# Sheet1.net
KiCad netlist of a schematic drawn in Altium Designer
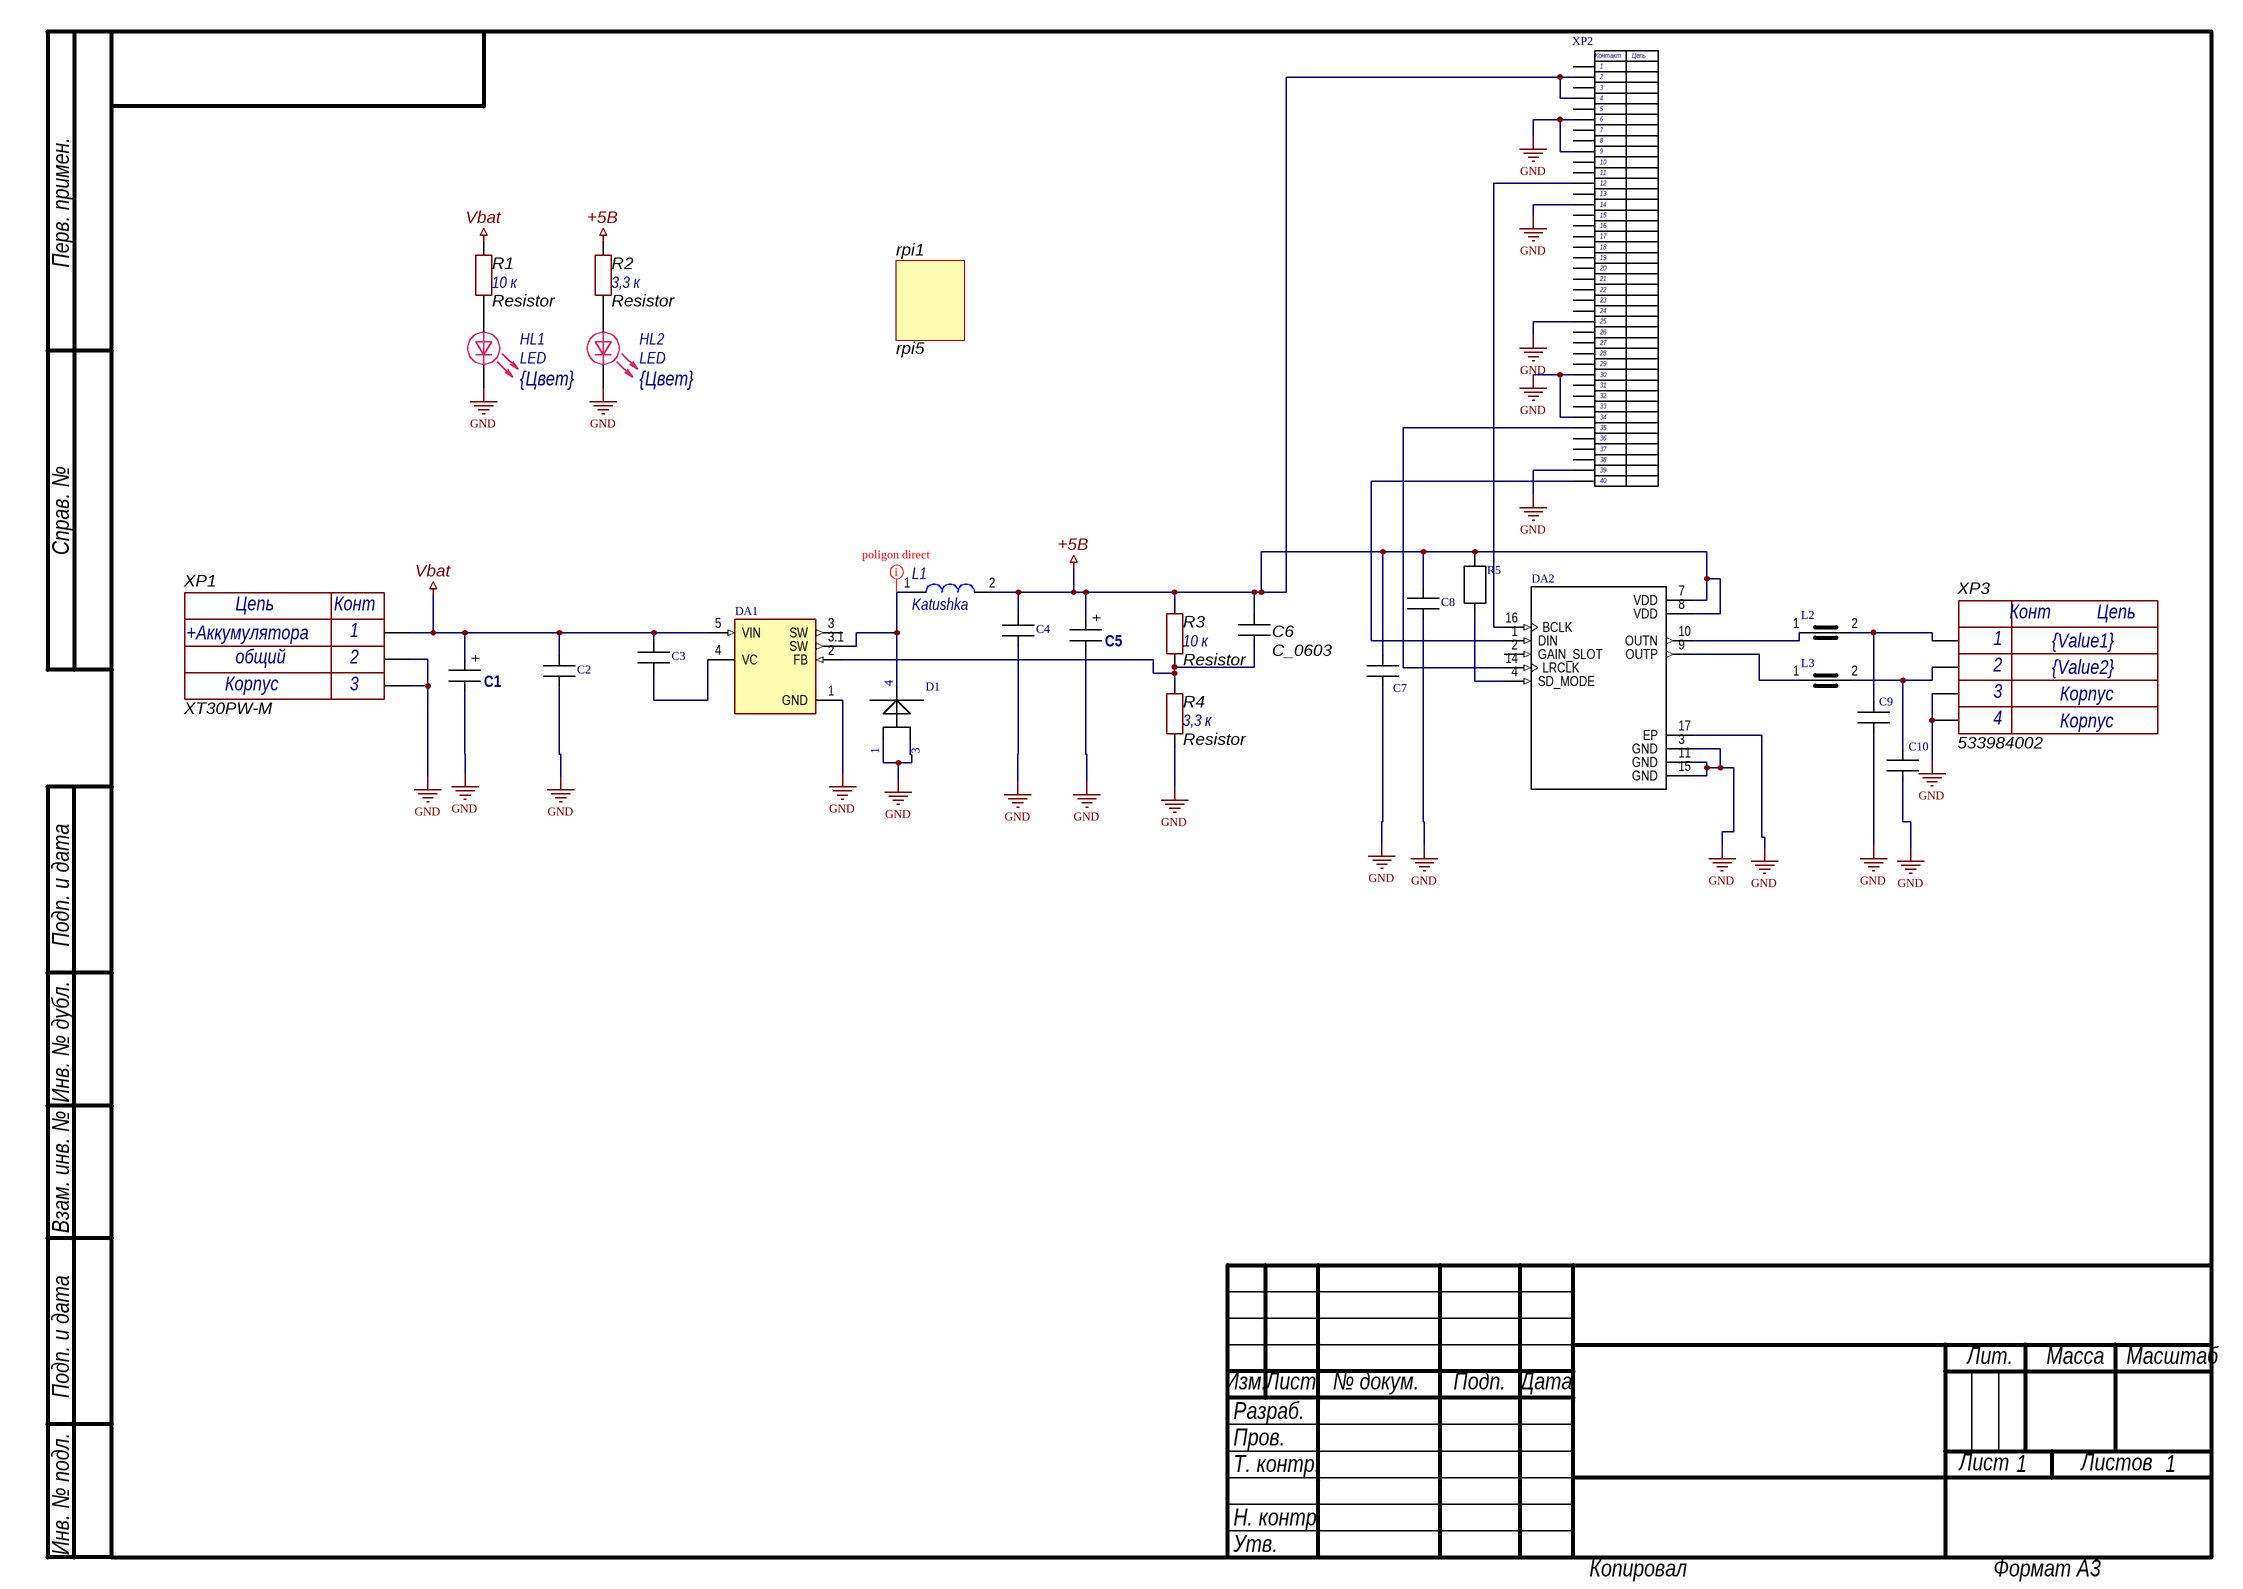
[diagram p0: Sheet1.SchDoc]

(export (version "E")
  (design (tool "Eeschema 10.0.6"))
  (components
    (comp (ref "C1")
      (value "C Al SMD 220mcF")
      (footprint "ECAP 10-10")
      (description "Конденсатор ECAP")
      (libsource (lib "Schlib1") (part "C Al SMD"))
    )
    (comp (ref "C2")
      (value "С_0.1uF")
      (footprint "CAP 0603 3D")
      (description "0.1мкФ")
      (libsource (lib "Schlib1") (part "С_0603"))
    )
    (comp (ref "C3")
      (value "С_0.1uF")
      (footprint "CAP 0603 3D")
      (description "0.1мкФ")
      (libsource (lib "Schlib1") (part "С_0603"))
    )
    (comp (ref "C4")
      (value "С_0.1uF")
      (footprint "CAP 0603 3D")
      (description "0.1мкФ")
      (libsource (lib "Schlib1") (part "С_0603"))
    )
    (comp (ref "C5")
      (value "C Al SMD 220mkf")
      (footprint "ECAP 10-10")
      (description "Конденсатор ECAP")
      (libsource (lib "Schlib1") (part "C Al SMD"))
    )
    (comp (ref "C6")
      (value "С_0603")
      (footprint "CAP 0603 3D")
      (description "Конденсатор керамика 0.33нФ")
      (libsource (lib "Schlib1") (part "С_0603"))
    )
    (comp (ref "C7")
      (value "С_0.1uF")
      (footprint "CAP 0603 3D")
      (description "0.1мкФ")
      (libsource (lib "Schlib1") (part "С_0603"))
    )
    (comp (ref "C8")
      (value "С_0.1uF")
      (footprint "CAP 0603 3D")
      (description "0.1мкФ")
      (libsource (lib "Schlib1") (part "С_0603"))
    )
    (comp (ref "C9") (value "С_220pF") (footprint "CAP 0603 3D") (libsource (lib "Schlib1") (part "С_0603")))
    (comp (ref "C10") (value "С_220pF") (footprint "CAP 0603 3D") (libsource (lib "Schlib1") (part "С_0603")))
    (comp (ref "D1")
      (value "LF33CDT")
      (footprint "DPACK")
      (description "Linear Voltage Regulator IC Positive Fixed 1 Output 500mA DPAK")
      (fields (field (name "MF") "STMicroelectronics"))
      (libsource (lib "Schlib1") (part "LF33CDT"))
    )
    (comp (ref "DA1")
      (value "XL4015")
      (footprint "CONV_XL4015")
      (description "5A 180KHz 36V Buck DC to DC Converter")
      (fields (field (name "MF") "XLSEMI"))
      (libsource (lib "Schlib1") (part "XL4015"))
    )
    (comp (ref "DA2")
      (value "MAX98357AETE+T")
      (footprint "QFN50P300X300X80-17N")
      (description "Tiny, Low-Cost, PCM Class D Amplifier with Class AB Performance")
      (fields (field (name "MF") "Analog Devices"))
      (libsource (lib "Schlib1") (part "MAX98357AETE+T"))
    )
    (comp (ref "HL1")
      (value "LED")
      (footprint "0805D")
      (description "Светодиод")
      (fields (field (name "COLOR") "{Цвет}"))
      (libsource (lib "Hydrolib") (part "LED"))
    )
    (comp (ref "HL2")
      (value "LED")
      (footprint "0805D")
      (description "Светодиод")
      (fields (field (name "COLOR") "{Цвет}"))
      (libsource (lib "Hydrolib") (part "LED"))
    )
    (comp (ref "L1") (value "Katushka") (footprint "Katushka") (libsource (lib "Schlib1") (part "Katushka")))
    (comp (ref "L2")
      (value "Z")
      (footprint "Ferrit_1210")
      (description "Феррит")
      (libsource (lib "Schlib1") (part "Z"))
    )
    (comp (ref "L3")
      (value "Z")
      (footprint "Ferrit_1210")
      (description "Феррит")
      (libsource (lib "Schlib1") (part "Z"))
    )
    (comp (ref "R1")
      (value "Resistor")
      (footprint "0603R")
      (description "Резистор номиналом 10 кОм и точностью 1%")
      (fields
        (field (name "ALTIUM_VALUE") "10 к")
        (field (name "PART NUMBER") "Resistor_10k_1_0603")
        (field (name "TOLERANCE") "1%")
      )
      (libsource (lib "Hydrolib") (part "Resistor"))
    )
    (comp (ref "R2")
      (value "Resistor")
      (footprint "0603R")
      (description "Резистор номиналом 3,3 кОм и точностью 1%")
      (fields
        (field (name "ALTIUM_VALUE") "3,3 к")
        (field (name "PART NUMBER") "Resistor_3.3k_1_0603")
        (field (name "TOLERANCE") "1%")
      )
      (libsource (lib "Hydrolib") (part "Resistor"))
    )
    (comp (ref "R3")
      (value "Resistor")
      (footprint "0603R")
      (description "Резистор номиналом 10 кОм и точностью 1%")
      (fields
        (field (name "ALTIUM_VALUE") "10 к")
        (field (name "PART NUMBER") "Resistor_10k_1_0603")
        (field (name "TOLERANCE") "1%")
      )
      (libsource (lib "Hydrolib") (part "Resistor"))
    )
    (comp (ref "R4")
      (value "Resistor")
      (footprint "0603R")
      (description "Резистор номиналом 3,3 кОм и точностью 1%")
      (fields
        (field (name "ALTIUM_VALUE") "3,3 к")
        (field (name "PART NUMBER") "Resistor_3.3k_1_0603")
        (field (name "TOLERANCE") "1%")
      )
      (libsource (lib "Hydrolib") (part "Resistor"))
    )
    (comp (ref "R5") (value "R_0603") (footprint "Res_0603 3D") (libsource (lib "Schlib1") (part "R_0603")))
    (comp (ref "rpi1") (value "rpi5") (footprint "rpi5") (libsource (lib "Schlib1") (part "rpi5")))
    (comp (ref "XP1")
      (value "XT30PW-M")
      (footprint "XT30PW-M")
      (description "30 А (15 продолжительно), 2 контакта разъем угловой отец")
      (fields
        (field (name "VALUE3") "Корпус")
        (field (name "VALUE2") "общий")
        (field (name "VALUE1") "+Аккумулятора")
      )
      (libsource (lib "Hydrolib") (part "Polar_Conn_Shield"))
    )
    (comp (ref "XP2") (value "PBD_40") (footprint "PBD40_8.5") (libsource (lib "Schlib1") (part "PBD_40")))
    (comp (ref "XP3")
      (value "533984002")
      (footprint "Picoblade_533984002")
      (description "2pin, 1.25mm, вилка, PicoBlade, на плату, SMT")
      (fields
        (field (name "VALUE3") "Корпус")
        (field (name "VALUE2") "{Value2}")
        (field (name "VALUE4") "Корпус")
        (field (name "VALUE1") "{Value1}")
        (field (name "PART NUMBER") "Picoblade_533984002")
      )
      (libsource (lib "Hydrolib") (part "Conn_2pin_2shield"))
    )
  )
  (nets
    (net (code "1") (name "+5В") (class "Default")
      (node (ref "C4") (pin "1") (pinfunction "-_1") (pintype "passive"))
      (node (ref "C5") (pin "2") (pinfunction "+_2") (pintype "passive"))
      (node (ref "C6") (pin "1") (pinfunction "-_1") (pintype "passive"))
      (node (ref "C7") (pin "1") (pinfunction "-_1") (pintype "passive"))
      (node (ref "C8") (pin "1") (pinfunction "-_1") (pintype "passive"))
      (node (ref "DA2") (pin "7") (pinfunction "VDD_7") (pintype "power_in"))
      (node (ref "DA2") (pin "8") (pinfunction "VDD_8") (pintype "power_in"))
      (node (ref "L1") (pin "2") (pintype "passive"))
      (node (ref "R2") (pin "2") (pinfunction "2_2") (pintype "passive"))
      (node (ref "R3") (pin "2") (pinfunction "2_2") (pintype "passive"))
      (node (ref "R5") (pin "2") (pintype "passive"))
      (node (ref "XP2") (pin "2") (pinfunction "2_2") (pintype "passive"))
      (node (ref "XP2") (pin "4") (pinfunction "4_4") (pintype "passive"))
    )
    (net (code "2") (name "GND") (class "Default")
      (node (ref "C1") (pin "1") (pinfunction "-_1") (pintype "passive"))
      (node (ref "C10") (pin "2") (pinfunction "+_2") (pintype "passive"))
      (node (ref "C2") (pin "2") (pinfunction "+_2") (pintype "passive"))
      (node (ref "C4") (pin "2") (pinfunction "+_2") (pintype "passive"))
      (node (ref "C5") (pin "1") (pinfunction "-_1") (pintype "passive"))
      (node (ref "C7") (pin "2") (pinfunction "+_2") (pintype "passive"))
      (node (ref "C8") (pin "2") (pinfunction "+_2") (pintype "passive"))
      (node (ref "C9") (pin "2") (pinfunction "+_2") (pintype "passive"))
      (node (ref "D1") (pin "1") (pinfunction "1_1") (pintype "passive"))
      (node (ref "D1") (pin "3") (pinfunction "3_3") (pintype "passive"))
      (node (ref "DA1") (pin "1") (pinfunction "GND_1") (pintype "power_in"))
      (node (ref "DA2") (pin "11") (pinfunction "GND_11") (pintype "power_in"))
      (node (ref "DA2") (pin "15") (pinfunction "GND_15") (pintype "power_in"))
      (node (ref "DA2") (pin "17") (pinfunction "EP_17") (pintype "power_in"))
      (node (ref "DA2") (pin "3") (pinfunction "GND_3") (pintype "power_in"))
      (node (ref "HL1") (pin "2") (pinfunction "2_2") (pintype "passive"))
      (node (ref "HL2") (pin "2") (pinfunction "2_2") (pintype "passive"))
      (node (ref "R4") (pin "1") (pinfunction "1_1") (pintype "passive"))
      (node (ref "XP1") (pin "0") (pinfunction "0_0") (pintype "passive"))
      (node (ref "XP1") (pin "N") (pinfunction "N_N") (pintype "passive"))
      (node (ref "XP2") (pin "14") (pinfunction "14_14") (pintype "passive"))
      (node (ref "XP2") (pin "25") (pinfunction "25_25") (pintype "passive"))
      (node (ref "XP2") (pin "30") (pinfunction "30_30") (pintype "passive"))
      (node (ref "XP2") (pin "34") (pinfunction "34_34") (pintype "passive"))
      (node (ref "XP2") (pin "39") (pinfunction "39_39") (pintype "passive"))
      (node (ref "XP2") (pin "6") (pinfunction "6_6") (pintype "passive"))
      (node (ref "XP2") (pin "9") (pinfunction "9_9") (pintype "passive"))
      (node (ref "XP3") (pin "3") (pinfunction "3_3") (pintype "passive"))
      (node (ref "XP3") (pin "4") (pinfunction "4_4") (pintype "passive"))
    )
    (net (code "3") (name "Net-(C3-+)") (class "Default")
      (node (ref "C3") (pin "2") (pinfunction "+_2") (pintype "passive"))
      (node (ref "DA1") (pin "4") (pinfunction "VC_4") (pintype "passive"))
    )
    (net (code "4") (name "Net-(C6-+)") (class "Default")
      (node (ref "C6") (pin "2") (pinfunction "+_2") (pintype "passive"))
      (node (ref "DA1") (pin "2") (pinfunction "FB_2") (pintype "input"))
      (node (ref "R3") (pin "1") (pinfunction "1_1") (pintype "passive"))
      (node (ref "R4") (pin "2") (pinfunction "2_2") (pintype "passive"))
    )
    (net (code "5") (name "Net-(C9--)") (class "Default")
      (node (ref "C9") (pin "1") (pinfunction "-_1") (pintype "passive"))
      (node (ref "L2") (pin "2") (pinfunction "2_2") (pintype "passive"))
      (node (ref "XP3") (pin "1") (pinfunction "1_1") (pintype "passive"))
    )
    (net (code "6") (name "Net-(C10--)") (class "Default")
      (node (ref "C10") (pin "1") (pinfunction "-_1") (pintype "passive"))
      (node (ref "L3") (pin "2") (pinfunction "2_2") (pintype "passive"))
      (node (ref "XP3") (pin "2") (pinfunction "2_2") (pintype "passive"))
    )
    (net (code "7") (name "Net-(D1-GND)") (class "Default")
      (node (ref "D1") (pin "4") (pinfunction "GND_4") (pintype "passive"))
      (node (ref "DA1") (pin "3.1") (pinfunction "SW_3.1") (pintype "output"))
      (node (ref "L1") (pin "1") (pinfunction "0_1") (pintype "passive"))
    )
    (net (code "8") (name "Net-(DA2-BCLK)") (class "Default")
      (node (ref "DA2") (pin "16") (pinfunction "BCLK_16") (pintype "input"))
      (node (ref "XP2") (pin "12") (pinfunction "12_12") (pintype "passive"))
    )
    (net (code "9") (name "Net-(DA2-DIN)") (class "Default")
      (node (ref "DA2") (pin "1") (pinfunction "DIN_1") (pintype "input"))
      (node (ref "XP2") (pin "40") (pinfunction "40_40") (pintype "passive"))
    )
    (net (code "10") (name "Net-(DA2-LRCLK)") (class "Default")
      (node (ref "DA2") (pin "14") (pinfunction "LRCLK_14") (pintype "input"))
      (node (ref "XP2") (pin "35") (pinfunction "35_35") (pintype "passive"))
    )
    (net (code "11") (name "Net-(DA2-OUTN)") (class "Default")
      (node (ref "DA2") (pin "10") (pinfunction "OUTN_10") (pintype "output"))
      (node (ref "L2") (pin "1") (pinfunction "1_1") (pintype "passive"))
    )
    (net (code "12") (name "Net-(DA2-OUTP)") (class "Default")
      (node (ref "DA2") (pin "9") (pinfunction "OUTP_9") (pintype "output"))
      (node (ref "L3") (pin "1") (pinfunction "1_1") (pintype "passive"))
    )
    (net (code "13") (name "Net-(DA2-SD_MODE)") (class "Default")
      (node (ref "DA2") (pin "4") (pinfunction "SD_MODE_4") (pintype "input"))
      (node (ref "R5") (pin "1") (pintype "passive"))
    )
    (net (code "14") (name "Net-(HL1-Pad1)") (class "Default")
      (node (ref "HL1") (pin "1") (pinfunction "1_1") (pintype "passive"))
      (node (ref "R1") (pin "1") (pinfunction "1_1") (pintype "passive"))
    )
    (net (code "15") (name "Net-(HL2-Pad1)") (class "Default")
      (node (ref "HL2") (pin "1") (pinfunction "1_1") (pintype "passive"))
      (node (ref "R2") (pin "1") (pinfunction "1_1") (pintype "passive"))
    )
    (net (code "16") (name "Vbat") (class "Default")
      (node (ref "C1") (pin "2") (pinfunction "+_2") (pintype "passive"))
      (node (ref "C2") (pin "1") (pinfunction "-_1") (pintype "passive"))
      (node (ref "C3") (pin "1") (pinfunction "-_1") (pintype "passive"))
      (node (ref "DA1") (pin "5") (pinfunction "VIN_5") (pintype "input"))
      (node (ref "R1") (pin "2") (pinfunction "2_2") (pintype "passive"))
      (node (ref "XP1") (pin "P") (pinfunction "P_P") (pintype "passive"))
    )
    (net (code "17") (name "unconnected-(DA1-SW-Pad3)") (class "Default")
      (node (ref "DA1") (pin "3") (pinfunction "SW_3") (pintype "output"))
    )
    (net (code "18") (name "unconnected-(DA2-GAIN_SLOT-Pad2)") (class "Default")
      (node (ref "DA2") (pin "2") (pinfunction "GAIN_SLOT_2") (pintype "input"))
    )
    (net (code "19") (name "unconnected-(XP2-Pad1)") (class "Default")
      (node (ref "XP2") (pin "1") (pinfunction "1_1") (pintype "passive"))
    )
    (net (code "20") (name "unconnected-(XP2-Pad3)") (class "Default")
      (node (ref "XP2") (pin "3") (pinfunction "3_3") (pintype "passive"))
    )
    (net (code "21") (name "unconnected-(XP2-Pad5)") (class "Default")
      (node (ref "XP2") (pin "5") (pinfunction "5_5") (pintype "passive"))
    )
    (net (code "22") (name "unconnected-(XP2-Pad7)") (class "Default")
      (node (ref "XP2") (pin "7") (pinfunction "7_7") (pintype "passive"))
    )
    (net (code "23") (name "unconnected-(XP2-Pad8)") (class "Default")
      (node (ref "XP2") (pin "8") (pinfunction "8_8") (pintype "passive"))
    )
    (net (code "24") (name "unconnected-(XP2-Pad10)") (class "Default")
      (node (ref "XP2") (pin "10") (pinfunction "10_10") (pintype "passive"))
    )
    (net (code "25") (name "unconnected-(XP2-Pad11)") (class "Default")
      (node (ref "XP2") (pin "11") (pinfunction "11_11") (pintype "passive"))
    )
    (net (code "26") (name "unconnected-(XP2-Pad13)") (class "Default")
      (node (ref "XP2") (pin "13") (pinfunction "13_13") (pintype "passive"))
    )
    (net (code "27") (name "unconnected-(XP2-Pad15)") (class "Default")
      (node (ref "XP2") (pin "15") (pinfunction "15_15") (pintype "passive"))
    )
    (net (code "28") (name "unconnected-(XP2-Pad16)") (class "Default")
      (node (ref "XP2") (pin "16") (pinfunction "16_16") (pintype "passive"))
    )
    (net (code "29") (name "unconnected-(XP2-Pad17)") (class "Default")
      (node (ref "XP2") (pin "17") (pinfunction "17_17") (pintype "passive"))
    )
    (net (code "30") (name "unconnected-(XP2-Pad18)") (class "Default")
      (node (ref "XP2") (pin "18") (pinfunction "18_18") (pintype "passive"))
    )
    (net (code "31") (name "unconnected-(XP2-Pad19)") (class "Default")
      (node (ref "XP2") (pin "19") (pinfunction "19_19") (pintype "passive"))
    )
    (net (code "32") (name "unconnected-(XP2-Pad20)") (class "Default")
      (node (ref "XP2") (pin "20") (pinfunction "20_20") (pintype "passive"))
    )
    (net (code "33") (name "unconnected-(XP2-Pad21)") (class "Default")
      (node (ref "XP2") (pin "21") (pinfunction "21_21") (pintype "passive"))
    )
    (net (code "34") (name "unconnected-(XP2-Pad22)") (class "Default")
      (node (ref "XP2") (pin "22") (pinfunction "22_22") (pintype "passive"))
    )
    (net (code "35") (name "unconnected-(XP2-Pad23)") (class "Default")
      (node (ref "XP2") (pin "23") (pinfunction "23_23") (pintype "passive"))
    )
    (net (code "36") (name "unconnected-(XP2-Pad24)") (class "Default")
      (node (ref "XP2") (pin "24") (pinfunction "24_24") (pintype "passive"))
    )
    (net (code "37") (name "unconnected-(XP2-Pad26)") (class "Default")
      (node (ref "XP2") (pin "26") (pinfunction "26_26") (pintype "passive"))
    )
    (net (code "38") (name "unconnected-(XP2-Pad27)") (class "Default")
      (node (ref "XP2") (pin "27") (pinfunction "27_27") (pintype "passive"))
    )
    (net (code "39") (name "unconnected-(XP2-Pad28)") (class "Default")
      (node (ref "XP2") (pin "28") (pinfunction "28_28") (pintype "passive"))
    )
    (net (code "40") (name "unconnected-(XP2-Pad29)") (class "Default")
      (node (ref "XP2") (pin "29") (pinfunction "29_29") (pintype "passive"))
    )
    (net (code "41") (name "unconnected-(XP2-Pad31)") (class "Default")
      (node (ref "XP2") (pin "31") (pinfunction "31_31") (pintype "passive"))
    )
    (net (code "42") (name "unconnected-(XP2-Pad32)") (class "Default")
      (node (ref "XP2") (pin "32") (pinfunction "32_32") (pintype "passive"))
    )
    (net (code "43") (name "unconnected-(XP2-Pad33)") (class "Default")
      (node (ref "XP2") (pin "33") (pinfunction "33_33") (pintype "passive"))
    )
    (net (code "44") (name "unconnected-(XP2-Pad36)") (class "Default")
      (node (ref "XP2") (pin "36") (pinfunction "36_36") (pintype "passive"))
    )
    (net (code "45") (name "unconnected-(XP2-Pad37)") (class "Default")
      (node (ref "XP2") (pin "37") (pinfunction "37_37") (pintype "passive"))
    )
    (net (code "46") (name "unconnected-(XP2-Pad38)") (class "Default")
      (node (ref "XP2") (pin "38") (pinfunction "38_38") (pintype "passive"))
    )
  )
)
